# AD9838.net
KiCad netlist of a schematic drawn in Altium Designer
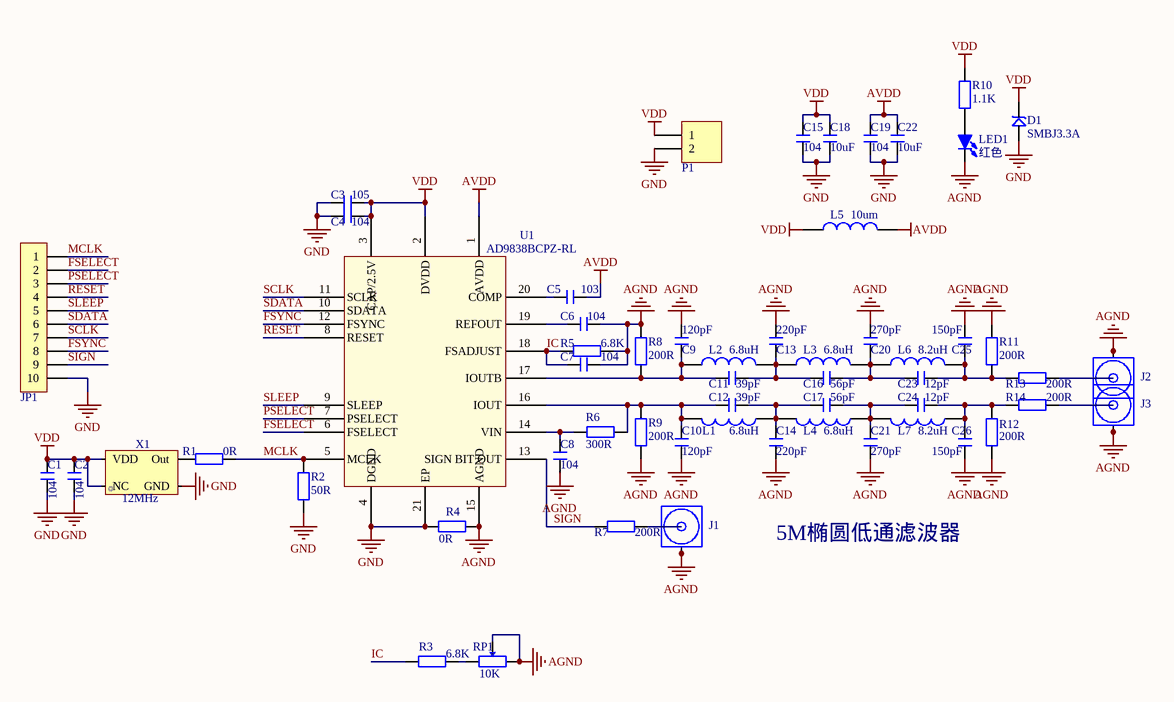
[diagram p0: AD9838模块.SchDoc]

(export (version "E")
  (design (tool "Eeschema 10.0.6"))
  (components
    (comp (ref "C1")
      (value "104")
      (footprint "0603P")
      (description "无极性贴片电容")
      (fields (field (name "版权归属") "源创客"))
      (libsource (lib "电阻-电容-电感") (part "C"))
    )
    (comp (ref "C2")
      (value "104")
      (footprint "0603P")
      (description "无极性贴片电容")
      (fields (field (name "版权归属") "源创客"))
      (libsource (lib "电阻-电容-电感") (part "C"))
    )
    (comp (ref "C3")
      (value "105")
      (footprint "0603P")
      (description "无极性贴片电容")
      (fields (field (name "版权归属") "源创客"))
      (libsource (lib "电阻-电容-电感") (part "C"))
    )
    (comp (ref "C4")
      (value "104")
      (footprint "0603P")
      (description "无极性贴片电容")
      (fields (field (name "版权归属") "源创客"))
      (libsource (lib "电阻-电容-电感") (part "C"))
    )
    (comp (ref "C5")
      (value "103")
      (footprint "0603P")
      (description "无极性贴片电容")
      (fields (field (name "版权归属") "源创客"))
      (libsource (lib "电阻-电容-电感") (part "C"))
    )
    (comp (ref "C6")
      (value "104")
      (footprint "0603P")
      (description "无极性贴片电容")
      (fields (field (name "版权归属") "源创客"))
      (libsource (lib "电阻-电容-电感") (part "C"))
    )
    (comp (ref "C7")
      (value "104")
      (footprint "0603P")
      (description "无极性贴片电容")
      (fields (field (name "版权归属") "源创客"))
      (libsource (lib "电阻-电容-电感") (part "C"))
    )
    (comp (ref "C8")
      (value "104")
      (footprint "0603P")
      (description "无极性贴片电容")
      (fields (field (name "版权归属") "源创客"))
      (libsource (lib "电阻-电容-电感") (part "C"))
    )
    (comp (ref "C9")
      (value "120pF")
      (footprint "0603P")
      (description "无极性贴片电容")
      (fields (field (name "版权归属") "源创客"))
      (libsource (lib "电阻-电容-电感") (part "C"))
    )
    (comp (ref "C10")
      (value "120pF")
      (footprint "0603P")
      (description "无极性贴片电容")
      (fields (field (name "版权归属") "源创客"))
      (libsource (lib "电阻-电容-电感") (part "C"))
    )
    (comp (ref "C11")
      (value "39pF")
      (footprint "0603P")
      (description "无极性贴片电容")
      (fields (field (name "版权归属") "源创客"))
      (libsource (lib "电阻-电容-电感") (part "C"))
    )
    (comp (ref "C12")
      (value "39pF")
      (footprint "0603P")
      (description "无极性贴片电容")
      (fields (field (name "版权归属") "源创客"))
      (libsource (lib "电阻-电容-电感") (part "C"))
    )
    (comp (ref "C13")
      (value "220pF")
      (footprint "0603P")
      (description "无极性贴片电容")
      (fields (field (name "版权归属") "源创客"))
      (libsource (lib "电阻-电容-电感") (part "C"))
    )
    (comp (ref "C14")
      (value "220pF")
      (footprint "0603P")
      (description "无极性贴片电容")
      (fields (field (name "版权归属") "源创客"))
      (libsource (lib "电阻-电容-电感") (part "C"))
    )
    (comp (ref "C15")
      (value "104")
      (footprint "0603P")
      (description "无极性贴片电容")
      (fields (field (name "版权归属") "源创客"))
      (libsource (lib "电阻-电容-电感") (part "C"))
    )
    (comp (ref "C16")
      (value "56pF")
      (footprint "0603P")
      (description "无极性贴片电容")
      (fields (field (name "版权归属") "源创客"))
      (libsource (lib "电阻-电容-电感") (part "C"))
    )
    (comp (ref "C17")
      (value "56pF")
      (footprint "0603P")
      (description "无极性贴片电容")
      (fields (field (name "版权归属") "源创客"))
      (libsource (lib "电阻-电容-电感") (part "C"))
    )
    (comp (ref "C18")
      (value "10uF")
      (footprint "0603P")
      (description "无极性贴片电容")
      (fields (field (name "版权归属") "源创客"))
      (libsource (lib "电阻-电容-电感") (part "C"))
    )
    (comp (ref "C19")
      (value "104")
      (footprint "0603P")
      (description "无极性贴片电容")
      (fields (field (name "版权归属") "源创客"))
      (libsource (lib "电阻-电容-电感") (part "C"))
    )
    (comp (ref "C20")
      (value "270pF")
      (footprint "0603P")
      (description "无极性贴片电容")
      (fields (field (name "版权归属") "源创客"))
      (libsource (lib "电阻-电容-电感") (part "C"))
    )
    (comp (ref "C21")
      (value "270pF")
      (footprint "0603P")
      (description "无极性贴片电容")
      (fields (field (name "版权归属") "源创客"))
      (libsource (lib "电阻-电容-电感") (part "C"))
    )
    (comp (ref "C22")
      (value "10uF")
      (footprint "0603P")
      (description "无极性贴片电容")
      (fields (field (name "版权归属") "源创客"))
      (libsource (lib "电阻-电容-电感") (part "C"))
    )
    (comp (ref "C23")
      (value "12pF")
      (footprint "0603P")
      (description "无极性贴片电容")
      (fields (field (name "版权归属") "源创客"))
      (libsource (lib "电阻-电容-电感") (part "C"))
    )
    (comp (ref "C24")
      (value "12pF")
      (footprint "0603P")
      (description "无极性贴片电容")
      (fields (field (name "版权归属") "源创客"))
      (libsource (lib "电阻-电容-电感") (part "C"))
    )
    (comp (ref "C25")
      (value "150pF")
      (footprint "0603P")
      (description "无极性贴片电容")
      (fields (field (name "版权归属") "源创客"))
      (libsource (lib "电阻-电容-电感") (part "C"))
    )
    (comp (ref "C26")
      (value "150pF")
      (footprint "0603P")
      (description "无极性贴片电容")
      (fields (field (name "版权归属") "源创客"))
      (libsource (lib "电阻-电容-电感") (part "C"))
    )
    (comp (ref "D1")
      (value "SMBJ3.3A")
      (footprint "SMBJ")
      (description "TVS")
      (libsource (lib "阿波罗STM32F4&F7底板封装库") (part "SMBJ"))
    )
    (comp (ref "J1") (value "COAX") (footprint "MCX5.08-5-H") (libsource (lib "LIB") (part "COAX")))
    (comp (ref "J2") (value "COAX") (footprint "MCX5.08-5-H") (libsource (lib "LIB") (part "COAX")))
    (comp (ref "J3") (value "COAX") (footprint "MCX5.08-5-H") (libsource (lib "LIB") (part "COAX")))
    (comp (ref "JP1")
      (value "HDR-1X10")
      (footprint "HDR-1X10_H")
      (description "10P接插件")
      (fields (field (name "版权归属") "源创客"))
      (libsource (lib "接插件") (part "Header 10"))
    )
    (comp (ref "L1")
      (value "6.8uH")
      (footprint "0603P")
      (description "小功率贴片电感")
      (fields (field (name "版权归属") "源创客"))
      (libsource (lib "电阻-电容-电感") (part "L"))
    )
    (comp (ref "L2")
      (value "6.8uH")
      (footprint "0603P")
      (description "小功率贴片电感")
      (fields (field (name "版权归属") "源创客"))
      (libsource (lib "电阻-电容-电感") (part "L"))
    )
    (comp (ref "L3")
      (value "6.8uH")
      (footprint "0603P")
      (description "小功率贴片电感")
      (fields (field (name "版权归属") "源创客"))
      (libsource (lib "电阻-电容-电感") (part "L"))
    )
    (comp (ref "L4")
      (value "6.8uH")
      (footprint "0603P")
      (description "小功率贴片电感")
      (fields (field (name "版权归属") "源创客"))
      (libsource (lib "电阻-电容-电感") (part "L"))
    )
    (comp (ref "L5")
      (value "10um")
      (footprint "0603P")
      (description "小功率贴片电感")
      (fields (field (name "版权归属") "源创客"))
      (libsource (lib "电阻-电容-电感") (part "L"))
    )
    (comp (ref "L6")
      (value "8.2uH")
      (footprint "0603P")
      (description "小功率贴片电感")
      (fields (field (name "版权归属") "源创客"))
      (libsource (lib "电阻-电容-电感") (part "L"))
    )
    (comp (ref "L7")
      (value "8.2uH")
      (footprint "0603P")
      (description "小功率贴片电感")
      (fields (field (name "版权归属") "源创客"))
      (libsource (lib "电阻-电容-电感") (part "L"))
    )
    (comp (ref "LED1")
      (value "红色")
      (footprint "LED 0805G")
      (description "贴片LED")
      (fields (field (name "版权归属") "源创客"))
      (libsource (lib "LED") (part "LED-SMD"))
    )
    (comp (ref "P1")
      (value "Header 2")
      (footprint "HDR2X1_B2")
      (description "接插件")
      (fields (field (name "PUBLISHER") "Altium Limited"))
      (libsource (lib "LIB") (part "Header 2"))
    )
    (comp (ref "R1")
      (value "0R")
      (footprint "0603P")
      (description "贴片电阻")
      (fields (field (name "版权归属") "源创客"))
      (libsource (lib "电阻-电容-电感") (part "R"))
    )
    (comp (ref "R2")
      (value "50R")
      (footprint "0603P")
      (description "贴片电阻")
      (fields (field (name "版权归属") "源创客"))
      (libsource (lib "电阻-电容-电感") (part "R"))
    )
    (comp (ref "R3")
      (value "6.8K")
      (footprint "0603P")
      (description "贴片电阻")
      (fields (field (name "版权归属") "源创客"))
      (libsource (lib "电阻-电容-电感") (part "R"))
    )
    (comp (ref "R4")
      (value "0R")
      (footprint "0603P")
      (description "贴片电阻")
      (fields (field (name "版权归属") "源创客"))
      (libsource (lib "电阻-电容-电感") (part "R"))
    )
    (comp (ref "R5")
      (value "6.8K")
      (footprint "0603P")
      (description "贴片电阻")
      (fields (field (name "版权归属") "源创客"))
      (libsource (lib "电阻-电容-电感") (part "R"))
    )
    (comp (ref "R6")
      (value "300R")
      (footprint "0603P")
      (description "贴片电阻")
      (fields (field (name "版权归属") "源创客"))
      (libsource (lib "电阻-电容-电感") (part "R"))
    )
    (comp (ref "R7")
      (value "200R")
      (footprint "0603P")
      (description "贴片电阻")
      (fields (field (name "版权归属") "源创客"))
      (libsource (lib "电阻-电容-电感") (part "R"))
    )
    (comp (ref "R8")
      (value "200R")
      (footprint "0603P")
      (description "贴片电阻")
      (fields (field (name "版权归属") "源创客"))
      (libsource (lib "电阻-电容-电感") (part "R"))
    )
    (comp (ref "R9")
      (value "200R")
      (footprint "0603P")
      (description "贴片电阻")
      (fields (field (name "版权归属") "源创客"))
      (libsource (lib "电阻-电容-电感") (part "R"))
    )
    (comp (ref "R10")
      (value "1.1K")
      (footprint "0603P")
      (description "贴片电阻")
      (fields (field (name "版权归属") "源创客"))
      (libsource (lib "电阻-电容-电感") (part "R"))
    )
    (comp (ref "R11")
      (value "200R")
      (footprint "0603P")
      (description "贴片电阻")
      (fields (field (name "版权归属") "源创客"))
      (libsource (lib "电阻-电容-电感") (part "R"))
    )
    (comp (ref "R12")
      (value "200R")
      (footprint "0603P")
      (description "贴片电阻")
      (fields (field (name "版权归属") "源创客"))
      (libsource (lib "电阻-电容-电感") (part "R"))
    )
    (comp (ref "R13")
      (value "200R")
      (footprint "0603P")
      (description "贴片电阻")
      (fields (field (name "版权归属") "源创客"))
      (libsource (lib "电阻-电容-电感") (part "R"))
    )
    (comp (ref "R14")
      (value "200R")
      (footprint "0603P")
      (description "贴片电阻")
      (fields (field (name "版权归属") "源创客"))
      (libsource (lib "电阻-电容-电感") (part "R"))
    )
    (comp (ref "RP1")
      (value "10K")
      (footprint "3296W")
      (description "插件单联电位器")
      (fields (field (name "版权归属") "源创客"))
      (libsource (lib "电阻-电容-电感") (part "RP-ID"))
    )
    (comp (ref "U1")
      (value "AD9838BCPZ-RL")
      (footprint "CP_20_10")
      (description "DSS直接数字频率合成器")
      (libsource (lib "MyLibray") (part "AD9838BCPZ-RL"))
    )
    (comp (ref "X1")
      (value "XTAL")
      (footprint "X-CPX75")
      (description "有源晶振")
      (fields (field (name "FREQUENCY") "12MHz"))
      (libsource (lib "LIB") (part "XTAL_Oscillator"))
    )
  )
  (nets
    (net (code "1") (name "/FSELECT") (class "Default")
      (node (ref "JP1") (pin "2") (pinfunction "2_2") (pintype "passive"))
      (node (ref "U1") (pin "6") (pinfunction "FSELECT_6") (pintype "passive"))
    )
    (net (code "2") (name "/FSYNC") (class "Default")
      (node (ref "JP1") (pin "8") (pinfunction "8_8") (pintype "passive"))
      (node (ref "U1") (pin "12") (pinfunction "FSYNC_12") (pintype "passive"))
    )
    (net (code "3") (name "/IC") (class "Default")
      (node (ref "C7") (pin "2") (pinfunction "2_2") (pintype "passive"))
      (node (ref "R3") (pin "2") (pinfunction "2_2") (pintype "passive"))
      (node (ref "R5") (pin "2") (pinfunction "2_2") (pintype "passive"))
      (node (ref "U1") (pin "18") (pinfunction "FSADJUST_18") (pintype "passive"))
    )
    (net (code "4") (name "/MCLK") (class "Default")
      (node (ref "JP1") (pin "1") (pinfunction "1_1") (pintype "passive"))
      (node (ref "R1") (pin "1") (pinfunction "1_1") (pintype "passive"))
      (node (ref "R2") (pin "1") (pinfunction "1_1") (pintype "passive"))
      (node (ref "U1") (pin "5") (pinfunction "MCLK_5") (pintype "passive"))
    )
    (net (code "5") (name "/PSELECT") (class "Default")
      (node (ref "JP1") (pin "3") (pinfunction "3_3") (pintype "passive"))
      (node (ref "U1") (pin "7") (pinfunction "PSELECT_7") (pintype "passive"))
    )
    (net (code "6") (name "/RESET") (class "Default")
      (node (ref "JP1") (pin "4") (pinfunction "4_4") (pintype "passive"))
      (node (ref "U1") (pin "8") (pinfunction "RESET_8") (pintype "passive"))
    )
    (net (code "7") (name "/SCLK") (class "Default")
      (node (ref "JP1") (pin "7") (pinfunction "7_7") (pintype "passive"))
      (node (ref "U1") (pin "11") (pinfunction "SCLK_11") (pintype "passive"))
    )
    (net (code "8") (name "/SDATA") (class "Default")
      (node (ref "JP1") (pin "6") (pinfunction "6_6") (pintype "passive"))
      (node (ref "U1") (pin "10") (pinfunction "SDATA_10") (pintype "passive"))
    )
    (net (code "9") (name "/SIGN") (class "Default")
      (node (ref "JP1") (pin "9") (pinfunction "9_9") (pintype "passive"))
      (node (ref "R7") (pin "2") (pinfunction "2_2") (pintype "passive"))
      (node (ref "U1") (pin "13") (pinfunction "SIGN_BIT_OUT_13") (pintype "passive"))
    )
    (net (code "10") (name "/SLEEP") (class "Default")
      (node (ref "JP1") (pin "5") (pinfunction "5_5") (pintype "passive"))
      (node (ref "U1") (pin "9") (pinfunction "SLEEP_9") (pintype "passive"))
    )
    (net (code "11") (name "AGND") (class "Default")
      (node (ref "C10") (pin "1") (pinfunction "1_1") (pintype "passive"))
      (node (ref "C13") (pin "1") (pinfunction "1_1") (pintype "passive"))
      (node (ref "C14") (pin "1") (pinfunction "1_1") (pintype "passive"))
      (node (ref "C20") (pin "1") (pinfunction "1_1") (pintype "passive"))
      (node (ref "C21") (pin "1") (pinfunction "1_1") (pintype "passive"))
      (node (ref "C25") (pin "1") (pinfunction "1_1") (pintype "passive"))
      (node (ref "C26") (pin "1") (pinfunction "1_1") (pintype "passive"))
      (node (ref "C6") (pin "1") (pinfunction "1_1") (pintype "passive"))
      (node (ref "C7") (pin "1") (pinfunction "1_1") (pintype "passive"))
      (node (ref "C8") (pin "1") (pinfunction "1_1") (pintype "passive"))
      (node (ref "C9") (pin "1") (pinfunction "1_1") (pintype "passive"))
      (node (ref "J1") (pin "2") (pinfunction "GND_2") (pintype "passive"))
      (node (ref "J1") (pin "3") (pinfunction "GND_3") (pintype "passive"))
      (node (ref "J1") (pin "4") (pinfunction "GND_4") (pintype "passive"))
      (node (ref "J1") (pin "5") (pinfunction "GND_5") (pintype "passive"))
      (node (ref "J2") (pin "2") (pinfunction "GND_2") (pintype "passive"))
      (node (ref "J2") (pin "3") (pinfunction "GND_3") (pintype "passive"))
      (node (ref "J2") (pin "4") (pinfunction "GND_4") (pintype "passive"))
      (node (ref "J2") (pin "5") (pinfunction "GND_5") (pintype "passive"))
      (node (ref "J3") (pin "2") (pinfunction "GND_2") (pintype "passive"))
      (node (ref "J3") (pin "3") (pinfunction "GND_3") (pintype "passive"))
      (node (ref "J3") (pin "4") (pinfunction "GND_4") (pintype "passive"))
      (node (ref "J3") (pin "5") (pinfunction "GND_5") (pintype "passive"))
      (node (ref "LED1") (pin "2") (pinfunction "K_2") (pintype "passive"))
      (node (ref "R11") (pin "2") (pinfunction "2_2") (pintype "passive"))
      (node (ref "R12") (pin "2") (pinfunction "2_2") (pintype "passive"))
      (node (ref "R4") (pin "1") (pinfunction "1_1") (pintype "passive"))
      (node (ref "R5") (pin "1") (pinfunction "1_1") (pintype "passive"))
      (node (ref "R8") (pin "2") (pinfunction "2_2") (pintype "passive"))
      (node (ref "R9") (pin "1") (pinfunction "1_1") (pintype "passive"))
      (node (ref "RP1") (pin "2") (pinfunction "2_2") (pintype "passive"))
      (node (ref "RP1") (pin "3") (pinfunction "3_3") (pintype "passive"))
      (node (ref "U1") (pin "15") (pinfunction "AGND_15") (pintype "passive"))
    )
    (net (code "12") (name "AVDD") (class "Default")
      (node (ref "C19") (pin "2") (pinfunction "2_2") (pintype "passive"))
      (node (ref "C22") (pin "2") (pinfunction "2_2") (pintype "passive"))
      (node (ref "C5") (pin "1") (pinfunction "1_1") (pintype "passive"))
      (node (ref "L5") (pin "2") (pinfunction "2_2") (pintype "passive"))
      (node (ref "U1") (pin "1") (pinfunction "AVDD_1") (pintype "passive"))
    )
    (net (code "13") (name "GND") (class "Default")
      (node (ref "C1") (pin "2") (pinfunction "2_2") (pintype "passive"))
      (node (ref "C15") (pin "1") (pinfunction "1_1") (pintype "passive"))
      (node (ref "C18") (pin "1") (pinfunction "1_1") (pintype "passive"))
      (node (ref "C19") (pin "1") (pinfunction "1_1") (pintype "passive"))
      (node (ref "C2") (pin "2") (pinfunction "2_2") (pintype "passive"))
      (node (ref "C22") (pin "1") (pinfunction "1_1") (pintype "passive"))
      (node (ref "C3") (pin "2") (pinfunction "2_2") (pintype "passive"))
      (node (ref "C4") (pin "2") (pinfunction "2_2") (pintype "passive"))
      (node (ref "D1") (pin "1") (pintype "passive"))
      (node (ref "JP1") (pin "10") (pinfunction "10_10") (pintype "passive"))
      (node (ref "P1") (pin "2") (pinfunction "2_2") (pintype "passive"))
      (node (ref "R2") (pin "2") (pinfunction "2_2") (pintype "passive"))
      (node (ref "R4") (pin "2") (pinfunction "2_2") (pintype "passive"))
      (node (ref "U1") (pin "21") (pinfunction "EP_21") (pintype "passive"))
      (node (ref "U1") (pin "4") (pinfunction "DGND_4") (pintype "passive"))
      (node (ref "X1") (pin "2") (pinfunction "GND_2") (pintype "passive"))
    )
    (net (code "14") (name "Net-(C11-Pad2)") (class "Default")
      (node (ref "C11") (pin "2") (pinfunction "2_2") (pintype "passive"))
      (node (ref "C13") (pin "2") (pinfunction "2_2") (pintype "passive"))
      (node (ref "C16") (pin "1") (pinfunction "1_1") (pintype "passive"))
      (node (ref "L2") (pin "2") (pinfunction "2_2") (pintype "passive"))
      (node (ref "L3") (pin "1") (pinfunction "1_1") (pintype "passive"))
    )
    (net (code "15") (name "Net-(C12-Pad1)") (class "Default")
      (node (ref "C12") (pin "1") (pinfunction "1_1") (pintype "passive"))
      (node (ref "C14") (pin "2") (pinfunction "2_2") (pintype "passive"))
      (node (ref "C17") (pin "2") (pinfunction "2_2") (pintype "passive"))
      (node (ref "L1") (pin "1") (pinfunction "1_1") (pintype "passive"))
      (node (ref "L4") (pin "2") (pinfunction "2_2") (pintype "passive"))
    )
    (net (code "16") (name "Net-(C16-Pad2)") (class "Default")
      (node (ref "C16") (pin "2") (pinfunction "2_2") (pintype "passive"))
      (node (ref "C20") (pin "2") (pinfunction "2_2") (pintype "passive"))
      (node (ref "C23") (pin "1") (pinfunction "1_1") (pintype "passive"))
      (node (ref "L3") (pin "2") (pinfunction "2_2") (pintype "passive"))
      (node (ref "L6") (pin "1") (pinfunction "1_1") (pintype "passive"))
    )
    (net (code "17") (name "Net-(C17-Pad1)") (class "Default")
      (node (ref "C17") (pin "1") (pinfunction "1_1") (pintype "passive"))
      (node (ref "C21") (pin "2") (pinfunction "2_2") (pintype "passive"))
      (node (ref "C24") (pin "2") (pinfunction "2_2") (pintype "passive"))
      (node (ref "L4") (pin "1") (pinfunction "1_1") (pintype "passive"))
      (node (ref "L7") (pin "2") (pinfunction "2_2") (pintype "passive"))
    )
    (net (code "18") (name "Net-(C23-Pad2)") (class "Default")
      (node (ref "C23") (pin "2") (pinfunction "2_2") (pintype "passive"))
      (node (ref "C25") (pin "2") (pinfunction "2_2") (pintype "passive"))
      (node (ref "L6") (pin "2") (pinfunction "2_2") (pintype "passive"))
      (node (ref "R11") (pin "1") (pinfunction "1_1") (pintype "passive"))
      (node (ref "R13") (pin "2") (pinfunction "2_2") (pintype "passive"))
    )
    (net (code "19") (name "Net-(C24-Pad1)") (class "Default")
      (node (ref "C24") (pin "1") (pinfunction "1_1") (pintype "passive"))
      (node (ref "C26") (pin "2") (pinfunction "2_2") (pintype "passive"))
      (node (ref "L7") (pin "1") (pinfunction "1_1") (pintype "passive"))
      (node (ref "R12") (pin "1") (pinfunction "1_1") (pintype "passive"))
      (node (ref "R14") (pin "2") (pinfunction "2_2") (pintype "passive"))
    )
    (net (code "20") (name "Net-(J1-Signal)") (class "Default")
      (node (ref "J1") (pin "1") (pinfunction "Signal_1") (pintype "passive"))
      (node (ref "R7") (pin "1") (pinfunction "1_1") (pintype "passive"))
    )
    (net (code "21") (name "Net-(J2-Signal)") (class "Default")
      (node (ref "J2") (pin "1") (pinfunction "Signal_1") (pintype "passive"))
      (node (ref "R13") (pin "1") (pinfunction "1_1") (pintype "passive"))
    )
    (net (code "22") (name "Net-(J3-Signal)") (class "Default")
      (node (ref "J3") (pin "1") (pinfunction "Signal_1") (pintype "passive"))
      (node (ref "R14") (pin "1") (pinfunction "1_1") (pintype "passive"))
    )
    (net (code "23") (name "Net-(LED1-A)") (class "Default")
      (node (ref "LED1") (pin "1") (pinfunction "A_1") (pintype "passive"))
      (node (ref "R10") (pin "1") (pinfunction "1_1") (pintype "passive"))
    )
    (net (code "24") (name "Net-(R3-Pad1)") (class "Default")
      (node (ref "R3") (pin "1") (pinfunction "1_1") (pintype "passive"))
      (node (ref "RP1") (pin "1") (pinfunction "1_1") (pintype "passive"))
    )
    (net (code "25") (name "Net-(U1-COMP)") (class "Default")
      (node (ref "C5") (pin "2") (pinfunction "2_2") (pintype "passive"))
      (node (ref "U1") (pin "20") (pinfunction "COMP_20") (pintype "passive"))
    )
    (net (code "26") (name "Net-(U1-IOUT)") (class "Default")
      (node (ref "C10") (pin "2") (pinfunction "2_2") (pintype "passive"))
      (node (ref "C12") (pin "2") (pinfunction "2_2") (pintype "passive"))
      (node (ref "L1") (pin "2") (pinfunction "2_2") (pintype "passive"))
      (node (ref "R6") (pin "1") (pinfunction "1_1") (pintype "passive"))
      (node (ref "R9") (pin "2") (pinfunction "2_2") (pintype "passive"))
      (node (ref "U1") (pin "16") (pinfunction "IOUT_16") (pintype "passive"))
    )
    (net (code "27") (name "Net-(U1-IOUTB)") (class "Default")
      (node (ref "C11") (pin "1") (pinfunction "1_1") (pintype "passive"))
      (node (ref "C9") (pin "2") (pinfunction "2_2") (pintype "passive"))
      (node (ref "L2") (pin "1") (pinfunction "1_1") (pintype "passive"))
      (node (ref "R8") (pin "1") (pinfunction "1_1") (pintype "passive"))
      (node (ref "U1") (pin "17") (pinfunction "IOUTB_17") (pintype "passive"))
    )
    (net (code "28") (name "Net-(U1-REFOUT)") (class "Default")
      (node (ref "C6") (pin "2") (pinfunction "2_2") (pintype "passive"))
      (node (ref "U1") (pin "19") (pinfunction "REFOUT_19") (pintype "passive"))
    )
    (net (code "29") (name "Net-(U1-VIN)") (class "Default")
      (node (ref "C8") (pin "2") (pinfunction "2_2") (pintype "passive"))
      (node (ref "R6") (pin "2") (pinfunction "2_2") (pintype "passive"))
      (node (ref "U1") (pin "14") (pinfunction "VIN_14") (pintype "passive"))
    )
    (net (code "30") (name "Net-(X1-Out)") (class "Default")
      (node (ref "R1") (pin "2") (pinfunction "2_2") (pintype "passive"))
      (node (ref "X1") (pin "3") (pinfunction "Out_3") (pintype "passive"))
    )
    (net (code "31") (name "VDD") (class "Default")
      (node (ref "C1") (pin "1") (pinfunction "1_1") (pintype "passive"))
      (node (ref "C15") (pin "2") (pinfunction "2_2") (pintype "passive"))
      (node (ref "C18") (pin "2") (pinfunction "2_2") (pintype "passive"))
      (node (ref "C2") (pin "1") (pinfunction "1_1") (pintype "passive"))
      (node (ref "C3") (pin "1") (pinfunction "1_1") (pintype "passive"))
      (node (ref "C4") (pin "1") (pinfunction "1_1") (pintype "passive"))
      (node (ref "D1") (pin "2") (pintype "passive"))
      (node (ref "L5") (pin "1") (pinfunction "1_1") (pintype "passive"))
      (node (ref "P1") (pin "1") (pinfunction "1_1") (pintype "passive"))
      (node (ref "R10") (pin "2") (pinfunction "2_2") (pintype "passive"))
      (node (ref "U1") (pin "2") (pinfunction "DVDD_2") (pintype "passive"))
      (node (ref "U1") (pin "3") (pinfunction "CAP/2.5V_3") (pintype "passive"))
      (node (ref "X1") (pin "1") (pinfunction "NC_1") (pintype "passive"))
      (node (ref "X1") (pin "4") (pinfunction "VDD_4") (pintype "passive"))
    )
  )
)
